# 8x8_stm32.net
KiCad netlist of a schematic drawn in EAGLE
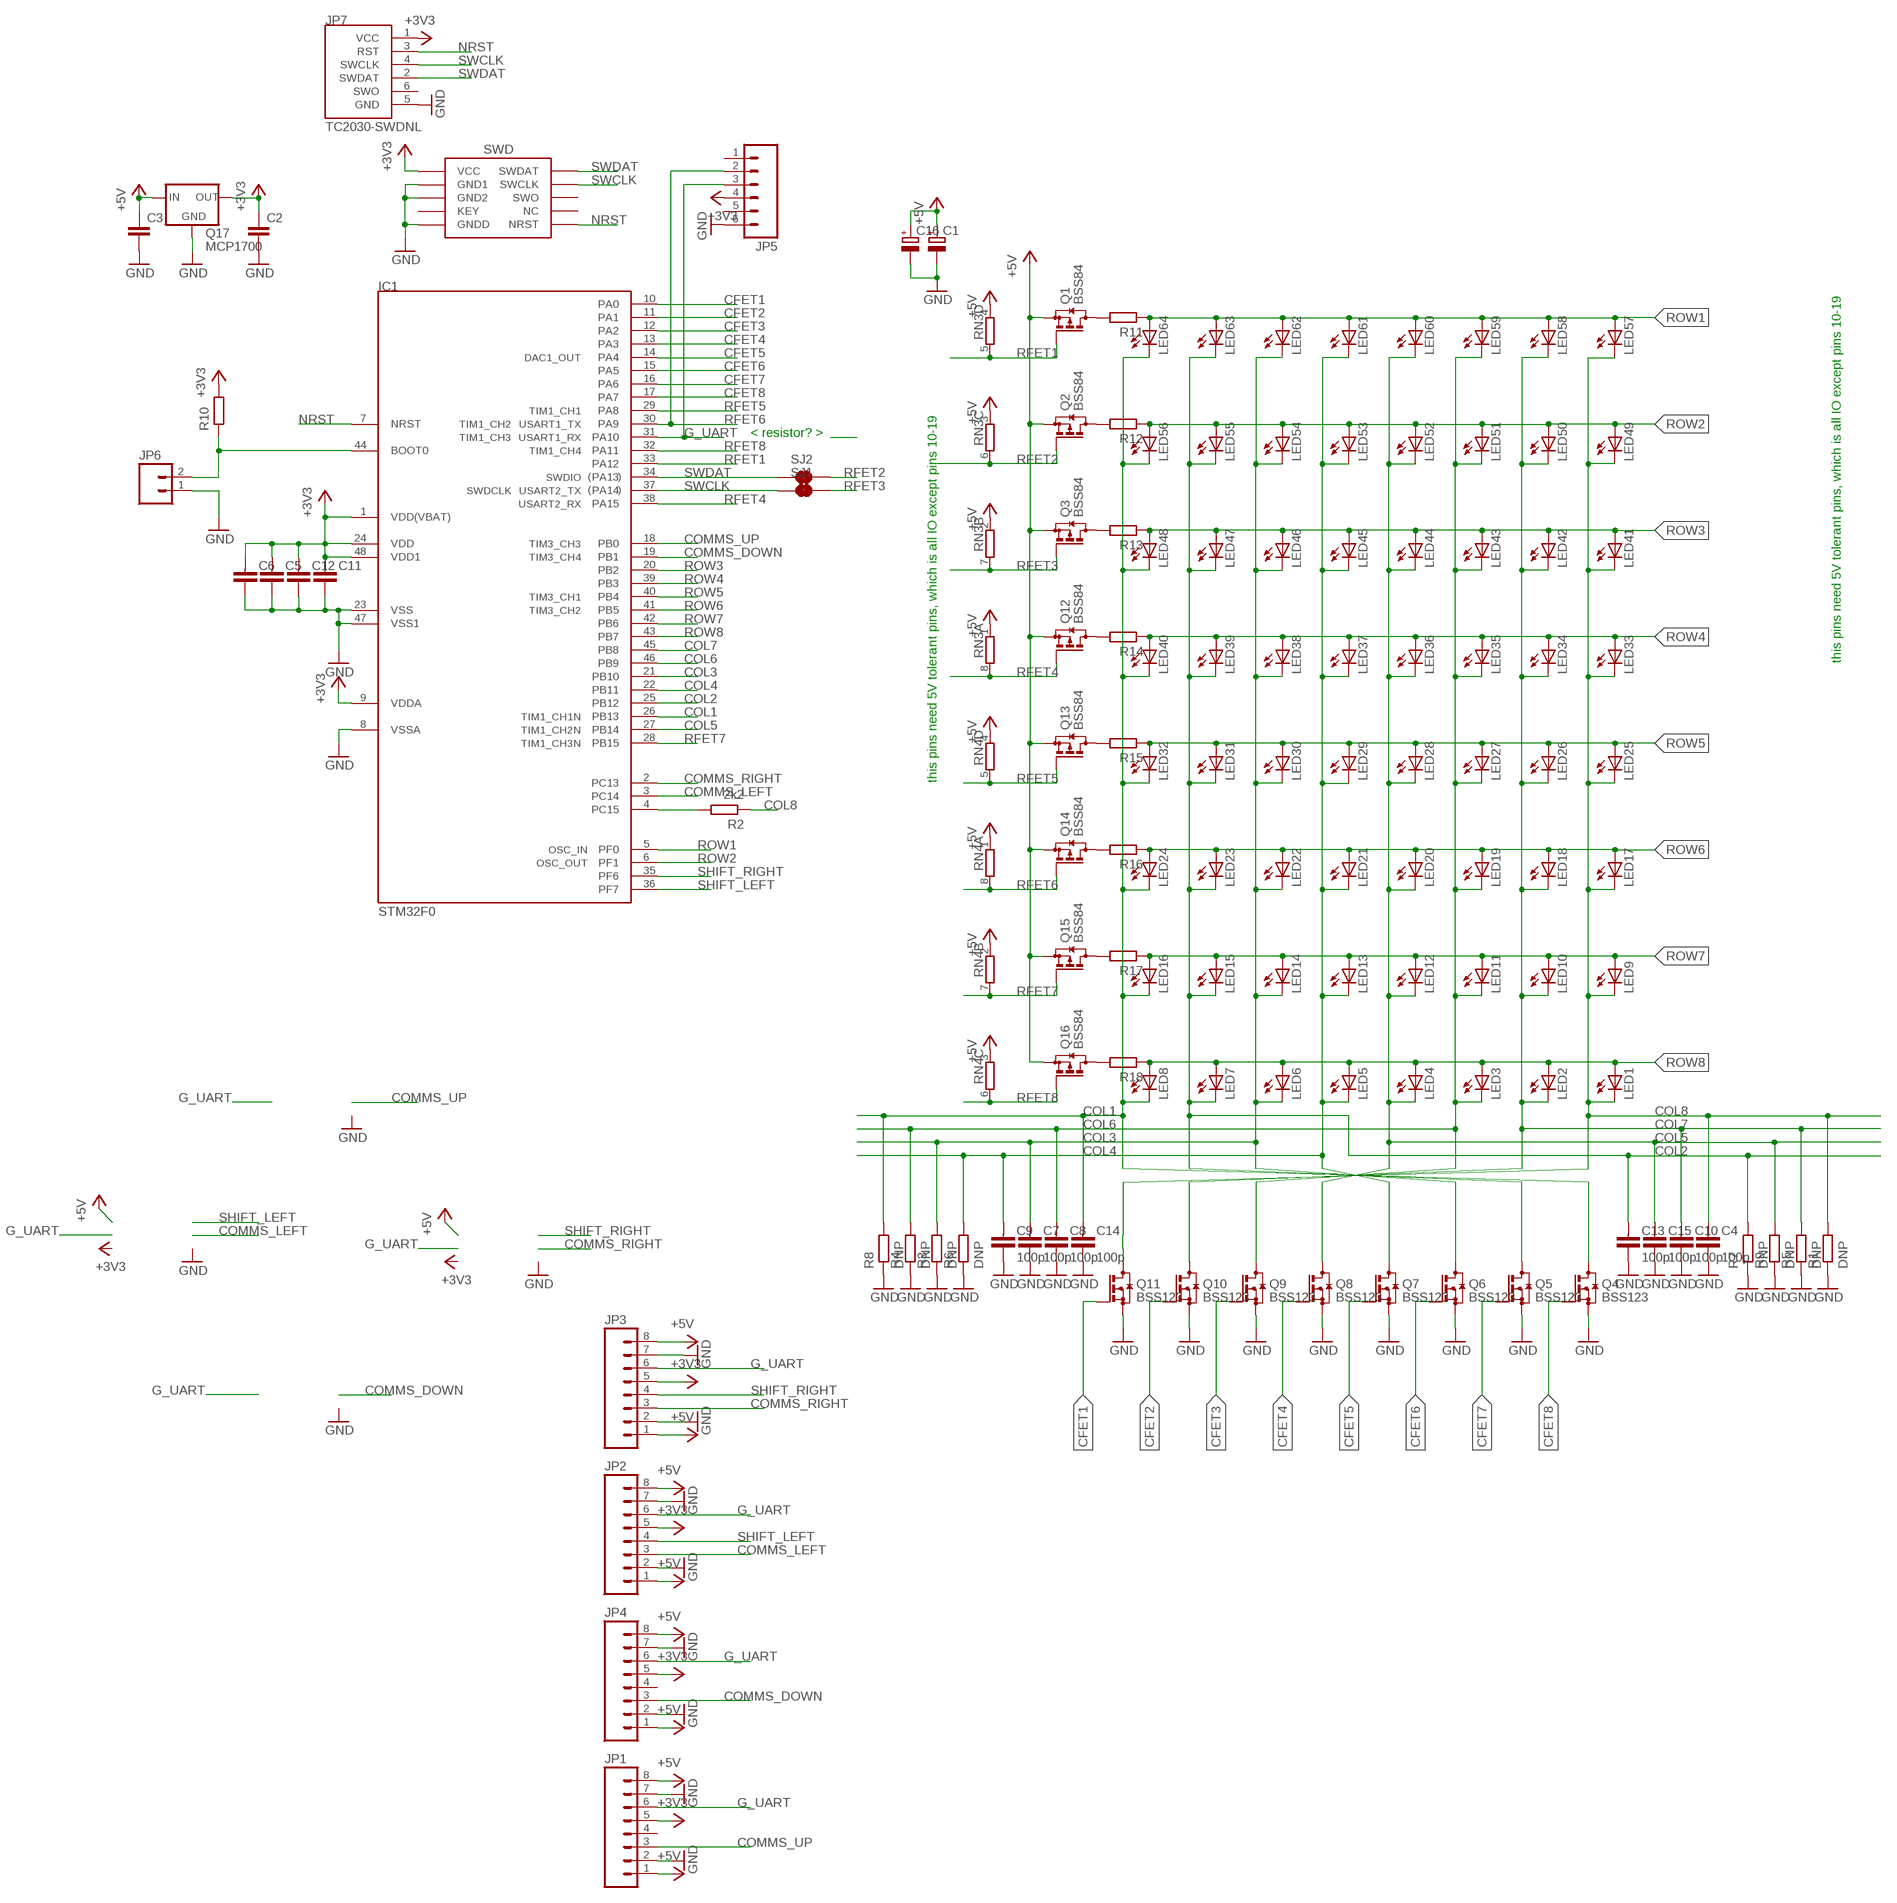
[diagram p0: schematic, sheet 1]

(export (version "E")
  (design (tool "Eeschema 10.0.6"))
  (components
    (comp (ref "C1")
      (value "CPOL-EUE2-4")
      (footprint "eagle-import:E2-4")
      (libsource (lib "eagle-import") (part "CPOL-EUE2-4"))
    )
    (comp (ref "C2")
      (value "C-EU050-025X075")
      (footprint "eagle-import:C050-025X075")
      (libsource (lib "eagle-import") (part "C-EU050-025X075"))
    )
    (comp (ref "C3")
      (value "C-EU050-025X075")
      (footprint "eagle-import:C050-025X075")
      (libsource (lib "eagle-import") (part "C-EU050-025X075"))
    )
    (comp (ref "C4")
      (value "100p")
      (footprint "eagle-import:C0603-N")
      (libsource (lib "eagle-import") (part "CAPACITOR0603-N"))
    )
    (comp (ref "C5")
      (value "CAPACITOR0603-N")
      (footprint "eagle-import:C0603-N")
      (libsource (lib "eagle-import") (part "CAPACITOR0603-N"))
    )
    (comp (ref "C6")
      (value "CAPACITOR0603-N")
      (footprint "eagle-import:C0603-N")
      (libsource (lib "eagle-import") (part "CAPACITOR0603-N"))
    )
    (comp (ref "C7")
      (value "100p")
      (footprint "eagle-import:C0603-N")
      (libsource (lib "eagle-import") (part "CAPACITOR0603-N"))
    )
    (comp (ref "C8")
      (value "100p")
      (footprint "eagle-import:C0603-N")
      (libsource (lib "eagle-import") (part "CAPACITOR0603-N"))
    )
    (comp (ref "C9")
      (value "100p")
      (footprint "eagle-import:C0603-N")
      (libsource (lib "eagle-import") (part "CAPACITOR0603-N"))
    )
    (comp (ref "C10")
      (value "100p")
      (footprint "eagle-import:C0603-N")
      (libsource (lib "eagle-import") (part "CAPACITOR0603-N"))
    )
    (comp (ref "C11")
      (value "CAPACITOR0603-N")
      (footprint "eagle-import:C0603-N")
      (libsource (lib "eagle-import") (part "CAPACITOR0603-N"))
    )
    (comp (ref "C12")
      (value "CAPACITOR0603-N")
      (footprint "eagle-import:C0603-N")
      (libsource (lib "eagle-import") (part "CAPACITOR0603-N"))
    )
    (comp (ref "C13")
      (value "100p")
      (footprint "eagle-import:C0603-N")
      (libsource (lib "eagle-import") (part "CAPACITOR0603-N"))
    )
    (comp (ref "C14")
      (value "100p")
      (footprint "eagle-import:C0603-N")
      (libsource (lib "eagle-import") (part "CAPACITOR0603-N"))
    )
    (comp (ref "C15")
      (value "100p")
      (footprint "eagle-import:C0603-N")
      (libsource (lib "eagle-import") (part "CAPACITOR0603-N"))
    )
    (comp (ref "C16")
      (value "CPOL-EUE2-4")
      (footprint "eagle-import:E2-4")
      (libsource (lib "eagle-import") (part "CPOL-EUE2-4"))
    )
    (comp (ref "IC1")
      (value "STM32F0")
      (footprint "eagle-import:TQFP48")
      (libsource (lib "eagle-import") (part "STM32F0"))
    )
    (comp (ref "J1")
      (value "SWD_SHROUD")
      (footprint "eagle-import:SWD_PTH_SHROUD")
      (libsource (lib "eagle-import") (part "SWD_SHROUD"))
    )
    (comp (ref "JP1")
      (value "M08")
      (footprint "eagle-import:1X08_ROUND")
      (libsource (lib "eagle-import") (part "M08"))
    )
    (comp (ref "JP2")
      (value "M08")
      (footprint "eagle-import:1X08_ROUND")
      (libsource (lib "eagle-import") (part "M08"))
    )
    (comp (ref "JP3")
      (value "M08")
      (footprint "eagle-import:1X08_ROUND")
      (libsource (lib "eagle-import") (part "M08"))
    )
    (comp (ref "JP4")
      (value "M08")
      (footprint "eagle-import:1X08_ROUND")
      (libsource (lib "eagle-import") (part "M08"))
    )
    (comp (ref "JP5")
      (value "M06SILK_FEMALE_PTH")
      (footprint "eagle-import:1X06")
      (libsource (lib "eagle-import") (part "M06SILK_FEMALE_PTH"))
    )
    (comp (ref "JP6")
      (value "M02PTH")
      (footprint "eagle-import:1X02")
      (libsource (lib "eagle-import") (part "M02PTH"))
    )
    (comp (ref "JP7")
      (value "TC2030-SWDNL")
      (footprint "eagle-import:TC2030-MCP-NL")
      (libsource (lib "eagle-import") (part "TC2030-SWDNL"))
    )
    (comp (ref "LED1")
      (value "LED5MM/0603")
      (footprint "eagle-import:LED5MM_SMD")
      (libsource (lib "eagle-import") (part "LED5MM/0603"))
    )
    (comp (ref "LED2")
      (value "LED5MM/0603")
      (footprint "eagle-import:LED5MM_SMD")
      (libsource (lib "eagle-import") (part "LED5MM/0603"))
    )
    (comp (ref "LED3")
      (value "LED5MM/0603")
      (footprint "eagle-import:LED5MM_SMD")
      (libsource (lib "eagle-import") (part "LED5MM/0603"))
    )
    (comp (ref "LED4")
      (value "LED5MM/0603")
      (footprint "eagle-import:LED5MM_SMD")
      (libsource (lib "eagle-import") (part "LED5MM/0603"))
    )
    (comp (ref "LED5")
      (value "LED5MM/0603")
      (footprint "eagle-import:LED5MM_SMD")
      (libsource (lib "eagle-import") (part "LED5MM/0603"))
    )
    (comp (ref "LED6")
      (value "LED5MM/0603")
      (footprint "eagle-import:LED5MM_SMD")
      (libsource (lib "eagle-import") (part "LED5MM/0603"))
    )
    (comp (ref "LED7")
      (value "LED5MM/0603")
      (footprint "eagle-import:LED5MM_SMD")
      (libsource (lib "eagle-import") (part "LED5MM/0603"))
    )
    (comp (ref "LED8")
      (value "LED5MM/0603")
      (footprint "eagle-import:LED5MM_SMD")
      (libsource (lib "eagle-import") (part "LED5MM/0603"))
    )
    (comp (ref "LED9")
      (value "LED5MM/0603")
      (footprint "eagle-import:LED5MM_SMD")
      (libsource (lib "eagle-import") (part "LED5MM/0603"))
    )
    (comp (ref "LED10")
      (value "LED5MM/0603")
      (footprint "eagle-import:LED5MM_SMD")
      (libsource (lib "eagle-import") (part "LED5MM/0603"))
    )
    (comp (ref "LED11")
      (value "LED5MM/0603")
      (footprint "eagle-import:LED5MM_SMD")
      (libsource (lib "eagle-import") (part "LED5MM/0603"))
    )
    (comp (ref "LED12")
      (value "LED5MM/0603")
      (footprint "eagle-import:LED5MM_SMD")
      (libsource (lib "eagle-import") (part "LED5MM/0603"))
    )
    (comp (ref "LED13")
      (value "LED5MM/0603")
      (footprint "eagle-import:LED5MM_SMD")
      (libsource (lib "eagle-import") (part "LED5MM/0603"))
    )
    (comp (ref "LED14")
      (value "LED5MM/0603")
      (footprint "eagle-import:LED5MM_SMD")
      (libsource (lib "eagle-import") (part "LED5MM/0603"))
    )
    (comp (ref "LED15")
      (value "LED5MM/0603")
      (footprint "eagle-import:LED5MM_SMD")
      (libsource (lib "eagle-import") (part "LED5MM/0603"))
    )
    (comp (ref "LED16")
      (value "LED5MM/0603")
      (footprint "eagle-import:LED5MM_SMD")
      (libsource (lib "eagle-import") (part "LED5MM/0603"))
    )
    (comp (ref "LED17")
      (value "LED5MM/0603")
      (footprint "eagle-import:LED5MM_SMD")
      (libsource (lib "eagle-import") (part "LED5MM/0603"))
    )
    (comp (ref "LED18")
      (value "LED5MM/0603")
      (footprint "eagle-import:LED5MM_SMD")
      (libsource (lib "eagle-import") (part "LED5MM/0603"))
    )
    (comp (ref "LED19")
      (value "LED5MM/0603")
      (footprint "eagle-import:LED5MM_SMD")
      (libsource (lib "eagle-import") (part "LED5MM/0603"))
    )
    (comp (ref "LED20")
      (value "LED5MM/0603")
      (footprint "eagle-import:LED5MM_SMD")
      (libsource (lib "eagle-import") (part "LED5MM/0603"))
    )
    (comp (ref "LED21")
      (value "LED5MM/0603")
      (footprint "eagle-import:LED5MM_SMD")
      (libsource (lib "eagle-import") (part "LED5MM/0603"))
    )
    (comp (ref "LED22")
      (value "LED5MM/0603")
      (footprint "eagle-import:LED5MM_SMD")
      (libsource (lib "eagle-import") (part "LED5MM/0603"))
    )
    (comp (ref "LED23")
      (value "LED5MM/0603")
      (footprint "eagle-import:LED5MM_SMD")
      (libsource (lib "eagle-import") (part "LED5MM/0603"))
    )
    (comp (ref "LED24")
      (value "LED5MM/0603")
      (footprint "eagle-import:LED5MM_SMD")
      (libsource (lib "eagle-import") (part "LED5MM/0603"))
    )
    (comp (ref "LED25")
      (value "LED5MM/0603")
      (footprint "eagle-import:LED5MM_SMD")
      (libsource (lib "eagle-import") (part "LED5MM/0603"))
    )
    (comp (ref "LED26")
      (value "LED5MM/0603")
      (footprint "eagle-import:LED5MM_SMD")
      (libsource (lib "eagle-import") (part "LED5MM/0603"))
    )
    (comp (ref "LED27")
      (value "LED5MM/0603")
      (footprint "eagle-import:LED5MM_SMD")
      (libsource (lib "eagle-import") (part "LED5MM/0603"))
    )
    (comp (ref "LED28")
      (value "LED5MM/0603")
      (footprint "eagle-import:LED5MM_SMD")
      (libsource (lib "eagle-import") (part "LED5MM/0603"))
    )
    (comp (ref "LED29")
      (value "LED5MM/0603")
      (footprint "eagle-import:LED5MM_SMD")
      (libsource (lib "eagle-import") (part "LED5MM/0603"))
    )
    (comp (ref "LED30")
      (value "LED5MM/0603")
      (footprint "eagle-import:LED5MM_SMD")
      (libsource (lib "eagle-import") (part "LED5MM/0603"))
    )
    (comp (ref "LED31")
      (value "LED5MM/0603")
      (footprint "eagle-import:LED5MM_SMD")
      (libsource (lib "eagle-import") (part "LED5MM/0603"))
    )
    (comp (ref "LED32")
      (value "LED5MM/0603")
      (footprint "eagle-import:LED5MM_SMD")
      (libsource (lib "eagle-import") (part "LED5MM/0603"))
    )
    (comp (ref "LED33")
      (value "LED5MM/0603")
      (footprint "eagle-import:LED5MM_SMD")
      (libsource (lib "eagle-import") (part "LED5MM/0603"))
    )
    (comp (ref "LED34")
      (value "LED5MM/0603")
      (footprint "eagle-import:LED5MM_SMD")
      (libsource (lib "eagle-import") (part "LED5MM/0603"))
    )
    (comp (ref "LED35")
      (value "LED5MM/0603")
      (footprint "eagle-import:LED5MM_SMD")
      (libsource (lib "eagle-import") (part "LED5MM/0603"))
    )
    (comp (ref "LED36")
      (value "LED5MM/0603")
      (footprint "eagle-import:LED5MM_SMD")
      (libsource (lib "eagle-import") (part "LED5MM/0603"))
    )
    (comp (ref "LED37")
      (value "LED5MM/0603")
      (footprint "eagle-import:LED5MM_SMD")
      (libsource (lib "eagle-import") (part "LED5MM/0603"))
    )
    (comp (ref "LED38")
      (value "LED5MM/0603")
      (footprint "eagle-import:LED5MM_SMD")
      (libsource (lib "eagle-import") (part "LED5MM/0603"))
    )
    (comp (ref "LED39")
      (value "LED5MM/0603")
      (footprint "eagle-import:LED5MM_SMD")
      (libsource (lib "eagle-import") (part "LED5MM/0603"))
    )
    (comp (ref "LED40")
      (value "LED5MM/0603")
      (footprint "eagle-import:LED5MM_SMD")
      (libsource (lib "eagle-import") (part "LED5MM/0603"))
    )
    (comp (ref "LED41")
      (value "LED5MM/0603")
      (footprint "eagle-import:LED5MM_SMD")
      (libsource (lib "eagle-import") (part "LED5MM/0603"))
    )
    (comp (ref "LED42")
      (value "LED5MM/0603")
      (footprint "eagle-import:LED5MM_SMD")
      (libsource (lib "eagle-import") (part "LED5MM/0603"))
    )
    (comp (ref "LED43")
      (value "LED5MM/0603")
      (footprint "eagle-import:LED5MM_SMD")
      (libsource (lib "eagle-import") (part "LED5MM/0603"))
    )
    (comp (ref "LED44")
      (value "LED5MM/0603")
      (footprint "eagle-import:LED5MM_SMD")
      (libsource (lib "eagle-import") (part "LED5MM/0603"))
    )
    (comp (ref "LED45")
      (value "LED5MM/0603")
      (footprint "eagle-import:LED5MM_SMD")
      (libsource (lib "eagle-import") (part "LED5MM/0603"))
    )
    (comp (ref "LED46")
      (value "LED5MM/0603")
      (footprint "eagle-import:LED5MM_SMD")
      (libsource (lib "eagle-import") (part "LED5MM/0603"))
    )
    (comp (ref "LED47")
      (value "LED5MM/0603")
      (footprint "eagle-import:LED5MM_SMD")
      (libsource (lib "eagle-import") (part "LED5MM/0603"))
    )
    (comp (ref "LED48")
      (value "LED5MM/0603")
      (footprint "eagle-import:LED5MM_SMD")
      (libsource (lib "eagle-import") (part "LED5MM/0603"))
    )
    (comp (ref "LED49")
      (value "LED5MM/0603")
      (footprint "eagle-import:LED5MM_SMD")
      (libsource (lib "eagle-import") (part "LED5MM/0603"))
    )
    (comp (ref "LED50")
      (value "LED5MM/0603")
      (footprint "eagle-import:LED5MM_SMD")
      (libsource (lib "eagle-import") (part "LED5MM/0603"))
    )
    (comp (ref "LED51")
      (value "LED5MM/0603")
      (footprint "eagle-import:LED5MM_SMD")
      (libsource (lib "eagle-import") (part "LED5MM/0603"))
    )
    (comp (ref "LED52")
      (value "LED5MM/0603")
      (footprint "eagle-import:LED5MM_SMD")
      (libsource (lib "eagle-import") (part "LED5MM/0603"))
    )
    (comp (ref "LED53")
      (value "LED5MM/0603")
      (footprint "eagle-import:LED5MM_SMD")
      (libsource (lib "eagle-import") (part "LED5MM/0603"))
    )
    (comp (ref "LED54")
      (value "LED5MM/0603")
      (footprint "eagle-import:LED5MM_SMD")
      (libsource (lib "eagle-import") (part "LED5MM/0603"))
    )
    (comp (ref "LED55")
      (value "LED5MM/0603")
      (footprint "eagle-import:LED5MM_SMD")
      (libsource (lib "eagle-import") (part "LED5MM/0603"))
    )
    (comp (ref "LED56")
      (value "LED5MM/0603")
      (footprint "eagle-import:LED5MM_SMD")
      (libsource (lib "eagle-import") (part "LED5MM/0603"))
    )
    (comp (ref "LED57")
      (value "LED5MM/0603")
      (footprint "eagle-import:LED5MM_SMD")
      (libsource (lib "eagle-import") (part "LED5MM/0603"))
    )
    (comp (ref "LED58")
      (value "LED5MM/0603")
      (footprint "eagle-import:LED5MM_SMD")
      (libsource (lib "eagle-import") (part "LED5MM/0603"))
    )
    (comp (ref "LED59")
      (value "LED5MM/0603")
      (footprint "eagle-import:LED5MM_SMD")
      (libsource (lib "eagle-import") (part "LED5MM/0603"))
    )
    (comp (ref "LED60")
      (value "LED5MM/0603")
      (footprint "eagle-import:LED5MM_SMD")
      (libsource (lib "eagle-import") (part "LED5MM/0603"))
    )
    (comp (ref "LED61")
      (value "LED5MM/0603")
      (footprint "eagle-import:LED5MM_SMD")
      (libsource (lib "eagle-import") (part "LED5MM/0603"))
    )
    (comp (ref "LED62")
      (value "LED5MM/0603")
      (footprint "eagle-import:LED5MM_SMD")
      (libsource (lib "eagle-import") (part "LED5MM/0603"))
    )
    (comp (ref "LED63")
      (value "LED5MM/0603")
      (footprint "eagle-import:LED5MM_SMD")
      (libsource (lib "eagle-import") (part "LED5MM/0603"))
    )
    (comp (ref "LED64")
      (value "LED5MM/0603")
      (footprint "eagle-import:LED5MM_SMD")
      (libsource (lib "eagle-import") (part "LED5MM/0603"))
    )
    (comp (ref "Q1")
      (value "BSS84")
      (footprint "eagle-import:SOT23")
      (libsource (lib "eagle-import") (part "BSS84"))
    )
    (comp (ref "Q2")
      (value "BSS84")
      (footprint "eagle-import:SOT23")
      (libsource (lib "eagle-import") (part "BSS84"))
    )
    (comp (ref "Q3")
      (value "BSS84")
      (footprint "eagle-import:SOT23")
      (libsource (lib "eagle-import") (part "BSS84"))
    )
    (comp (ref "Q4")
      (value "BSS123")
      (footprint "eagle-import:SOT23")
      (libsource (lib "eagle-import") (part "BSS123"))
    )
    (comp (ref "Q5")
      (value "BSS123")
      (footprint "eagle-import:SOT23")
      (libsource (lib "eagle-import") (part "BSS123"))
    )
    (comp (ref "Q6")
      (value "BSS123")
      (footprint "eagle-import:SOT23")
      (libsource (lib "eagle-import") (part "BSS123"))
    )
    (comp (ref "Q7")
      (value "BSS123")
      (footprint "eagle-import:SOT23")
      (libsource (lib "eagle-import") (part "BSS123"))
    )
    (comp (ref "Q8")
      (value "BSS123")
      (footprint "eagle-import:SOT23")
      (libsource (lib "eagle-import") (part "BSS123"))
    )
    (comp (ref "Q9")
      (value "BSS123")
      (footprint "eagle-import:SOT23")
      (libsource (lib "eagle-import") (part "BSS123"))
    )
    (comp (ref "Q10")
      (value "BSS123")
      (footprint "eagle-import:SOT23")
      (libsource (lib "eagle-import") (part "BSS123"))
    )
    (comp (ref "Q11")
      (value "BSS123")
      (footprint "eagle-import:SOT23")
      (libsource (lib "eagle-import") (part "BSS123"))
    )
    (comp (ref "Q12")
      (value "BSS84")
      (footprint "eagle-import:SOT23")
      (libsource (lib "eagle-import") (part "BSS84"))
    )
    (comp (ref "Q13")
      (value "BSS84")
      (footprint "eagle-import:SOT23")
      (libsource (lib "eagle-import") (part "BSS84"))
    )
    (comp (ref "Q14")
      (value "BSS84")
      (footprint "eagle-import:SOT23")
      (libsource (lib "eagle-import") (part "BSS84"))
    )
    (comp (ref "Q15")
      (value "BSS84")
      (footprint "eagle-import:SOT23")
      (libsource (lib "eagle-import") (part "BSS84"))
    )
    (comp (ref "Q16")
      (value "BSS84")
      (footprint "eagle-import:SOT23")
      (libsource (lib "eagle-import") (part "BSS84"))
    )
    (comp (ref "Q17")
      (value "MCP1700")
      (footprint "eagle-import:TO92-INLINE")
      (libsource (lib "eagle-import") (part "MCP1700"))
    )
    (comp (ref "R1")
      (value "DNP")
      (footprint "eagle-import:R0603-N")
      (libsource (lib "eagle-import") (part "RESISTOR0603-N"))
    )
    (comp (ref "R2")
      (value "2k2")
      (footprint "eagle-import:R0603-N")
      (libsource (lib "eagle-import") (part "RESISTOR0603-N"))
    )
    (comp (ref "R3")
      (value "DNP")
      (footprint "eagle-import:R0603-N")
      (libsource (lib "eagle-import") (part "RESISTOR0603-N"))
    )
    (comp (ref "R4")
      (value "DNP")
      (footprint "eagle-import:R0603-N")
      (libsource (lib "eagle-import") (part "RESISTOR0603-N"))
    )
    (comp (ref "R5")
      (value "DNP")
      (footprint "eagle-import:R0603-N")
      (libsource (lib "eagle-import") (part "RESISTOR0603-N"))
    )
    (comp (ref "R6")
      (value "DNP")
      (footprint "eagle-import:R0603-N")
      (libsource (lib "eagle-import") (part "RESISTOR0603-N"))
    )
    (comp (ref "R7")
      (value "DNP")
      (footprint "eagle-import:R0603-N")
      (libsource (lib "eagle-import") (part "RESISTOR0603-N"))
    )
    (comp (ref "R8")
      (value "DNP")
      (footprint "eagle-import:R0603-N")
      (libsource (lib "eagle-import") (part "RESISTOR0603-N"))
    )
    (comp (ref "R9")
      (value "DNP")
      (footprint "eagle-import:R0603-N")
      (libsource (lib "eagle-import") (part "RESISTOR0603-N"))
    )
    (comp (ref "R10")
      (value "RESISTOR0603-N")
      (footprint "eagle-import:R0603-N")
      (libsource (lib "eagle-import") (part "RESISTOR0603-N"))
    )
    (comp (ref "R11")
      (value "RESISTOR0603-N")
      (footprint "eagle-import:R0603-N")
      (libsource (lib "eagle-import") (part "RESISTOR0603-N"))
    )
    (comp (ref "R12")
      (value "RESISTOR0603-N")
      (footprint "eagle-import:R0603-N")
      (libsource (lib "eagle-import") (part "RESISTOR0603-N"))
    )
    (comp (ref "R13")
      (value "RESISTOR0603-N")
      (footprint "eagle-import:R0603-N")
      (libsource (lib "eagle-import") (part "RESISTOR0603-N"))
    )
    (comp (ref "R14")
      (value "RESISTOR0603-N")
      (footprint "eagle-import:R0603-N")
      (libsource (lib "eagle-import") (part "RESISTOR0603-N"))
    )
    (comp (ref "R15")
      (value "RESISTOR0603-N")
      (footprint "eagle-import:R0603-N")
      (libsource (lib "eagle-import") (part "RESISTOR0603-N"))
    )
    (comp (ref "R16")
      (value "RESISTOR0603-N")
      (footprint "eagle-import:R0603-N")
      (libsource (lib "eagle-import") (part "RESISTOR0603-N"))
    )
    (comp (ref "R17")
      (value "RESISTOR0603-N")
      (footprint "eagle-import:R0603-N")
      (libsource (lib "eagle-import") (part "RESISTOR0603-N"))
    )
    (comp (ref "R18")
      (value "RESISTOR0603-N")
      (footprint "eagle-import:R0603-N")
      (libsource (lib "eagle-import") (part "RESISTOR0603-N"))
    )
    (comp (ref "RN3")
      (value "4R-NEXB38V")
      (footprint "eagle-import:EXB38V")
      (libsource (lib "eagle-import") (part "4R-NEXB38V"))
    )
    (comp (ref "RN4")
      (value "4R-NEXB38V")
      (footprint "eagle-import:EXB38V")
      (libsource (lib "eagle-import") (part "4R-NEXB38V"))
    )
    (comp (ref "SJ1")
      (value "JUMPER-PAD-2-NC_BY_TRACE")
      (footprint "eagle-import:PAD-JUMPER-2-NC_BY_TRACE_YES_SILK")
      (libsource (lib "eagle-import") (part "JUMPER-PAD-2-NC_BY_TRACE"))
    )
    (comp (ref "SJ2")
      (value "JUMPER-PAD-2-NC_BY_TRACE")
      (footprint "eagle-import:PAD-JUMPER-2-NC_BY_TRACE_YES_SILK")
      (libsource (lib "eagle-import") (part "JUMPER-PAD-2-NC_BY_TRACE"))
    )
  )
  (nets
    (net (code "1") (name "+3V3") (class "Default")
      (node (ref "C11") (pin "1") (pinfunction "1_1") (pintype "passive"))
      (node (ref "C12") (pin "1") (pinfunction "1_1") (pintype "passive"))
      (node (ref "C2") (pin "1") (pinfunction "1_1") (pintype "passive"))
      (node (ref "C5") (pin "1") (pinfunction "1_1") (pintype "passive"))
      (node (ref "C6") (pin "1") (pinfunction "1_1") (pintype "passive"))
      (node (ref "IC1") (pin "1") (pinfunction "VDD(VBAT)_1") (pintype "power_in"))
      (node (ref "IC1") (pin "24") (pinfunction "VDD_24") (pintype "power_in"))
      (node (ref "IC1") (pin "48") (pinfunction "VDD1_48") (pintype "power_in"))
      (node (ref "IC1") (pin "9") (pinfunction "VDDA_9") (pintype "power_in"))
      (node (ref "J1") (pin "1") (pinfunction "VCC_1") (pintype "power_in"))
      (node (ref "JP1") (pin "5") (pinfunction "5_5") (pintype "passive"))
      (node (ref "JP2") (pin "5") (pinfunction "5_5") (pintype "passive"))
      (node (ref "JP3") (pin "5") (pinfunction "5_5") (pintype "passive"))
      (node (ref "JP4") (pin "5") (pinfunction "5_5") (pintype "passive"))
      (node (ref "JP5") (pin "4") (pinfunction "4_4") (pintype "passive"))
      (node (ref "JP7") (pin "1") (pinfunction "VCC_1") (pintype "power_in"))
      (node (ref "Q17") (pin "VOUT") (pinfunction "OUT_VOUT") (pintype "passive"))
      (node (ref "R10") (pin "2") (pinfunction "P$2_2") (pintype "passive"))
    )
    (net (code "2") (name "+5V") (class "Default")
      (node (ref "C1") (pin "+") (pinfunction "+_+") (pintype "passive"))
      (node (ref "C16") (pin "+") (pinfunction "+_+") (pintype "passive"))
      (node (ref "C3") (pin "1") (pinfunction "1_1") (pintype "passive"))
      (node (ref "JP1") (pin "1") (pinfunction "1_1") (pintype "passive"))
      (node (ref "JP1") (pin "8") (pinfunction "8_8") (pintype "passive"))
      (node (ref "JP2") (pin "1") (pinfunction "1_1") (pintype "passive"))
      (node (ref "JP2") (pin "8") (pinfunction "8_8") (pintype "passive"))
      (node (ref "JP3") (pin "1") (pinfunction "1_1") (pintype "passive"))
      (node (ref "JP3") (pin "8") (pinfunction "8_8") (pintype "passive"))
      (node (ref "JP4") (pin "1") (pinfunction "1_1") (pintype "passive"))
      (node (ref "JP4") (pin "8") (pinfunction "8_8") (pintype "passive"))
      (node (ref "Q1") (pin "2") (pinfunction "S_2") (pintype "passive"))
      (node (ref "Q12") (pin "2") (pinfunction "S_2") (pintype "passive"))
      (node (ref "Q13") (pin "2") (pinfunction "S_2") (pintype "passive"))
      (node (ref "Q14") (pin "2") (pinfunction "S_2") (pintype "passive"))
      (node (ref "Q15") (pin "2") (pinfunction "S_2") (pintype "passive"))
      (node (ref "Q16") (pin "2") (pinfunction "S_2") (pintype "passive"))
      (node (ref "Q17") (pin "VIN") (pinfunction "IN_VIN") (pintype "input"))
      (node (ref "Q2") (pin "2") (pinfunction "S_2") (pintype "passive"))
      (node (ref "Q3") (pin "2") (pinfunction "S_2") (pintype "passive"))
      (node (ref "RN3") (pin "1") (pinfunction "1_1") (pintype "passive"))
      (node (ref "RN3") (pin "2") (pinfunction "1_2") (pintype "passive"))
      (node (ref "RN3") (pin "3") (pinfunction "1_3") (pintype "passive"))
      (node (ref "RN3") (pin "4") (pinfunction "1_4") (pintype "passive"))
      (node (ref "RN4") (pin "1") (pinfunction "1_1") (pintype "passive"))
      (node (ref "RN4") (pin "2") (pinfunction "1_2") (pintype "passive"))
      (node (ref "RN4") (pin "3") (pinfunction "1_3") (pintype "passive"))
      (node (ref "RN4") (pin "4") (pinfunction "1_4") (pintype "passive"))
    )
    (net (code "3") (name "/COL1") (class "Default")
      (node (ref "C14") (pin "1") (pinfunction "1_1") (pintype "passive"))
      (node (ref "IC1") (pin "26") (pinfunction "PB13_26") (pintype "bidirectional"))
      (node (ref "LED16") (pin "K") (pinfunction "C_K") (pintype "passive"))
      (node (ref "LED16") (pin "K1") (pinfunction "C_K1") (pintype "passive"))
      (node (ref "LED24") (pin "K") (pinfunction "C_K") (pintype "passive"))
      (node (ref "LED24") (pin "K1") (pinfunction "C_K1") (pintype "passive"))
      (node (ref "LED32") (pin "K") (pinfunction "C_K") (pintype "passive"))
      (node (ref "LED32") (pin "K1") (pinfunction "C_K1") (pintype "passive"))
      (node (ref "LED40") (pin "K") (pinfunction "C_K") (pintype "passive"))
      (node (ref "LED40") (pin "K1") (pinfunction "C_K1") (pintype "passive"))
      (node (ref "LED48") (pin "K") (pinfunction "C_K") (pintype "passive"))
      (node (ref "LED48") (pin "K1") (pinfunction "C_K1") (pintype "passive"))
      (node (ref "LED56") (pin "K") (pinfunction "C_K") (pintype "passive"))
      (node (ref "LED56") (pin "K1") (pinfunction "C_K1") (pintype "passive"))
      (node (ref "LED64") (pin "K") (pinfunction "C_K") (pintype "passive"))
      (node (ref "LED64") (pin "K1") (pinfunction "C_K1") (pintype "passive"))
      (node (ref "LED8") (pin "K") (pinfunction "C_K") (pintype "passive"))
      (node (ref "LED8") (pin "K1") (pinfunction "C_K1") (pintype "passive"))
      (node (ref "Q4") (pin "3") (pinfunction "D_3") (pintype "passive"))
      (node (ref "R8") (pin "2") (pinfunction "P$2_2") (pintype "passive"))
    )
    (net (code "4") (name "/COL2") (class "Default")
      (node (ref "C13") (pin "1") (pinfunction "1_1") (pintype "passive"))
      (node (ref "IC1") (pin "25") (pinfunction "PB12_25") (pintype "bidirectional"))
      (node (ref "LED15") (pin "K") (pinfunction "C_K") (pintype "passive"))
      (node (ref "LED15") (pin "K1") (pinfunction "C_K1") (pintype "passive"))
      (node (ref "LED23") (pin "K") (pinfunction "C_K") (pintype "passive"))
      (node (ref "LED23") (pin "K1") (pinfunction "C_K1") (pintype "passive"))
      (node (ref "LED31") (pin "K") (pinfunction "C_K") (pintype "passive"))
      (node (ref "LED31") (pin "K1") (pinfunction "C_K1") (pintype "passive"))
      (node (ref "LED39") (pin "K") (pinfunction "C_K") (pintype "passive"))
      (node (ref "LED39") (pin "K1") (pinfunction "C_K1") (pintype "passive"))
      (node (ref "LED47") (pin "K") (pinfunction "C_K") (pintype "passive"))
      (node (ref "LED47") (pin "K1") (pinfunction "C_K1") (pintype "passive"))
      (node (ref "LED55") (pin "K") (pinfunction "C_K") (pintype "passive"))
      (node (ref "LED55") (pin "K1") (pinfunction "C_K1") (pintype "passive"))
      (node (ref "LED63") (pin "K") (pinfunction "C_K") (pintype "passive"))
      (node (ref "LED63") (pin "K1") (pinfunction "C_K1") (pintype "passive"))
      (node (ref "LED7") (pin "K") (pinfunction "C_K") (pintype "passive"))
      (node (ref "LED7") (pin "K1") (pinfunction "C_K1") (pintype "passive"))
      (node (ref "Q5") (pin "3") (pinfunction "D_3") (pintype "passive"))
      (node (ref "R7") (pin "2") (pinfunction "P$2_2") (pintype "passive"))
    )
    (net (code "5") (name "/COL3") (class "Default")
      (node (ref "C7") (pin "1") (pinfunction "1_1") (pintype "passive"))
      (node (ref "IC1") (pin "21") (pinfunction "PB10_21") (pintype "bidirectional"))
      (node (ref "LED14") (pin "K") (pinfunction "C_K") (pintype "passive"))
      (node (ref "LED14") (pin "K1") (pinfunction "C_K1") (pintype "passive"))
      (node (ref "LED22") (pin "K") (pinfunction "C_K") (pintype "passive"))
      (node (ref "LED22") (pin "K1") (pinfunction "C_K1") (pintype "passive"))
      (node (ref "LED30") (pin "K") (pinfunction "C_K") (pintype "passive"))
      (node (ref "LED30") (pin "K1") (pinfunction "C_K1") (pintype "passive"))
      (node (ref "LED38") (pin "K") (pinfunction "C_K") (pintype "passive"))
      (node (ref "LED38") (pin "K1") (pinfunction "C_K1") (pintype "passive"))
      (node (ref "LED46") (pin "K") (pinfunction "C_K") (pintype "passive"))
      (node (ref "LED46") (pin "K1") (pinfunction "C_K1") (pintype "passive"))
      (node (ref "LED54") (pin "K") (pinfunction "C_K") (pintype "passive"))
      (node (ref "LED54") (pin "K1") (pinfunction "C_K1") (pintype "passive"))
      (node (ref "LED6") (pin "K") (pinfunction "C_K") (pintype "passive"))
      (node (ref "LED6") (pin "K1") (pinfunction "C_K1") (pintype "passive"))
      (node (ref "LED62") (pin "K") (pinfunction "C_K") (pintype "passive"))
      (node (ref "LED62") (pin "K1") (pinfunction "C_K1") (pintype "passive"))
      (node (ref "Q6") (pin "3") (pinfunction "D_3") (pintype "passive"))
      (node (ref "R3") (pin "2") (pinfunction "P$2_2") (pintype "passive"))
    )
    (net (code "6") (name "/COL4") (class "Default")
      (node (ref "C9") (pin "1") (pinfunction "1_1") (pintype "passive"))
      (node (ref "IC1") (pin "22") (pinfunction "PB11_22") (pintype "bidirectional"))
      (node (ref "LED13") (pin "K") (pinfunction "C_K") (pintype "passive"))
      (node (ref "LED13") (pin "K1") (pinfunction "C_K1") (pintype "passive"))
      (node (ref "LED21") (pin "K") (pinfunction "C_K") (pintype "passive"))
      (node (ref "LED21") (pin "K1") (pinfunction "C_K1") (pintype "passive"))
      (node (ref "LED29") (pin "K") (pinfunction "C_K") (pintype "passive"))
      (node (ref "LED29") (pin "K1") (pinfunction "C_K1") (pintype "passive"))
      (node (ref "LED37") (pin "K") (pinfunction "C_K") (pintype "passive"))
      (node (ref "LED37") (pin "K1") (pinfunction "C_K1") (pintype "passive"))
      (node (ref "LED45") (pin "K") (pinfunction "C_K") (pintype "passive"))
      (node (ref "LED45") (pin "K1") (pinfunction "C_K1") (pintype "passive"))
      (node (ref "LED5") (pin "K") (pinfunction "C_K") (pintype "passive"))
      (node (ref "LED5") (pin "K1") (pinfunction "C_K1") (pintype "passive"))
      (node (ref "LED53") (pin "K") (pinfunction "C_K") (pintype "passive"))
      (node (ref "LED53") (pin "K1") (pinfunction "C_K1") (pintype "passive"))
      (node (ref "LED61") (pin "K") (pinfunction "C_K") (pintype "passive"))
      (node (ref "LED61") (pin "K1") (pinfunction "C_K1") (pintype "passive"))
      (node (ref "Q7") (pin "3") (pinfunction "D_3") (pintype "passive"))
      (node (ref "R6") (pin "2") (pinfunction "P$2_2") (pintype "passive"))
    )
    (net (code "7") (name "/COL5") (class "Default")
      (node (ref "C15") (pin "1") (pinfunction "1_1") (pintype "passive"))
      (node (ref "IC1") (pin "27") (pinfunction "PB14_27") (pintype "bidirectional"))
      (node (ref "LED12") (pin "K") (pinfunction "C_K") (pintype "passive"))
      (node (ref "LED12") (pin "K1") (pinfunction "C_K1") (pintype "passive"))
      (node (ref "LED20") (pin "K") (pinfunction "C_K") (pintype "passive"))
      (node (ref "LED20") (pin "K1") (pinfunction "C_K1") (pintype "passive"))
      (node (ref "LED28") (pin "K") (pinfunction "C_K") (pintype "passive"))
      (node (ref "LED28") (pin "K1") (pinfunction "C_K1") (pintype "passive"))
      (node (ref "LED36") (pin "K") (pinfunction "C_K") (pintype "passive"))
      (node (ref "LED36") (pin "K1") (pinfunction "C_K1") (pintype "passive"))
      (node (ref "LED4") (pin "K") (pinfunction "C_K") (pintype "passive"))
      (node (ref "LED4") (pin "K1") (pinfunction "C_K1") (pintype "passive"))
      (node (ref "LED44") (pin "K") (pinfunction "C_K") (pintype "passive"))
      (node (ref "LED44") (pin "K1") (pinfunction "C_K1") (pintype "passive"))
      (node (ref "LED52") (pin "K") (pinfunction "C_K") (pintype "passive"))
      (node (ref "LED52") (pin "K1") (pinfunction "C_K1") (pintype "passive"))
      (node (ref "LED60") (pin "K") (pinfunction "C_K") (pintype "passive"))
      (node (ref "LED60") (pin "K1") (pinfunction "C_K1") (pintype "passive"))
      (node (ref "Q8") (pin "3") (pinfunction "D_3") (pintype "passive"))
      (node (ref "R9") (pin "2") (pinfunction "P$2_2") (pintype "passive"))
    )
    (net (code "8") (name "/COL6") (class "Default")
      (node (ref "C8") (pin "1") (pinfunction "1_1") (pintype "passive"))
      (node (ref "IC1") (pin "46") (pinfunction "PB9_46") (pintype "bidirectional"))
      (node (ref "LED11") (pin "K") (pinfunction "C_K") (pintype "passive"))
      (node (ref "LED11") (pin "K1") (pinfunction "C_K1") (pintype "passive"))
      (node (ref "LED19") (pin "K") (pinfunction "C_K") (pintype "passive"))
      (node (ref "LED19") (pin "K1") (pinfunction "C_K1") (pintype "passive"))
      (node (ref "LED27") (pin "K") (pinfunction "C_K") (pintype "passive"))
      (node (ref "LED27") (pin "K1") (pinfunction "C_K1") (pintype "passive"))
      (node (ref "LED3") (pin "K") (pinfunction "C_K") (pintype "passive"))
      (node (ref "LED3") (pin "K1") (pinfunction "C_K1") (pintype "passive"))
      (node (ref "LED35") (pin "K") (pinfunction "C_K") (pintype "passive"))
      (node (ref "LED35") (pin "K1") (pinfunction "C_K1") (pintype "passive"))
      (node (ref "LED43") (pin "K") (pinfunction "C_K") (pintype "passive"))
      (node (ref "LED43") (pin "K1") (pinfunction "C_K1") (pintype "passive"))
      (node (ref "LED51") (pin "K") (pinfunction "C_K") (pintype "passive"))
      (node (ref "LED51") (pin "K1") (pinfunction "C_K1") (pintype "passive"))
      (node (ref "LED59") (pin "K") (pinfunction "C_K") (pintype "passive"))
      (node (ref "LED59") (pin "K1") (pinfunction "C_K1") (pintype "passive"))
      (node (ref "Q9") (pin "3") (pinfunction "D_3") (pintype "passive"))
      (node (ref "R4") (pin "2") (pinfunction "P$2_2") (pintype "passive"))
    )
    (net (code "9") (name "/COL7") (class "Default")
      (node (ref "C10") (pin "1") (pinfunction "1_1") (pintype "passive"))
      (node (ref "IC1") (pin "45") (pinfunction "PB8_45") (pintype "bidirectional"))
      (node (ref "LED10") (pin "K") (pinfunction "C_K") (pintype "passive"))
      (node (ref "LED10") (pin "K1") (pinfunction "C_K1") (pintype "passive"))
      (node (ref "LED18") (pin "K") (pinfunction "C_K") (pintype "passive"))
      (node (ref "LED18") (pin "K1") (pinfunction "C_K1") (pintype "passive"))
      (node (ref "LED2") (pin "K") (pinfunction "C_K") (pintype "passive"))
      (node (ref "LED2") (pin "K1") (pinfunction "C_K1") (pintype "passive"))
      (node (ref "LED26") (pin "K") (pinfunction "C_K") (pintype "passive"))
      (node (ref "LED26") (pin "K1") (pinfunction "C_K1") (pintype "passive"))
      (node (ref "LED34") (pin "K") (pinfunction "C_K") (pintype "passive"))
      (node (ref "LED34") (pin "K1") (pinfunction "C_K1") (pintype "passive"))
      (node (ref "LED42") (pin "K") (pinfunction "C_K") (pintype "passive"))
      (node (ref "LED42") (pin "K1") (pinfunction "C_K1") (pintype "passive"))
      (node (ref "LED50") (pin "K") (pinfunction "C_K") (pintype "passive"))
      (node (ref "LED50") (pin "K1") (pinfunction "C_K1") (pintype "passive"))
      (node (ref "LED58") (pin "K") (pinfunction "C_K") (pintype "passive"))
      (node (ref "LED58") (pin "K1") (pinfunction "C_K1") (pintype "passive"))
      (node (ref "Q10") (pin "3") (pinfunction "D_3") (pintype "passive"))
      (node (ref "R5") (pin "2") (pinfunction "P$2_2") (pintype "passive"))
    )
    (net (code "10") (name "/COL8") (class "Default")
      (node (ref "C4") (pin "1") (pinfunction "1_1") (pintype "passive"))
      (node (ref "LED1") (pin "K") (pinfunction "C_K") (pintype "passive"))
      (node (ref "LED1") (pin "K1") (pinfunction "C_K1") (pintype "passive"))
      (node (ref "LED17") (pin "K") (pinfunction "C_K") (pintype "passive"))
      (node (ref "LED17") (pin "K1") (pinfunction "C_K1") (pintype "passive"))
      (node (ref "LED25") (pin "K") (pinfunction "C_K") (pintype "passive"))
      (node (ref "LED25") (pin "K1") (pinfunction "C_K1") (pintype "passive"))
      (node (ref "LED33") (pin "K") (pinfunction "C_K") (pintype "passive"))
      (node (ref "LED33") (pin "K1") (pinfunction "C_K1") (pintype "passive"))
      (node (ref "LED41") (pin "K") (pinfunction "C_K") (pintype "passive"))
      (node (ref "LED41") (pin "K1") (pinfunction "C_K1") (pintype "passive"))
      (node (ref "LED49") (pin "K") (pinfunction "C_K") (pintype "passive"))
      (node (ref "LED49") (pin "K1") (pinfunction "C_K1") (pintype "passive"))
      (node (ref "LED57") (pin "K") (pinfunction "C_K") (pintype "passive"))
      (node (ref "LED57") (pin "K1") (pinfunction "C_K1") (pintype "passive"))
      (node (ref "LED9") (pin "K") (pinfunction "C_K") (pintype "passive"))
      (node (ref "LED9") (pin "K1") (pinfunction "C_K1") (pintype "passive"))
      (node (ref "Q11") (pin "3") (pinfunction "D_3") (pintype "passive"))
      (node (ref "R1") (pin "2") (pinfunction "P$2_2") (pintype "passive"))
      (node (ref "R2") (pin "1") (pinfunction "P$1_1") (pintype "passive"))
    )
    (net (code "11") (name "/COMMS_DOWN") (class "Default")
      (node (ref "IC1") (pin "19") (pinfunction "PB1_19") (pintype "bidirectional"))
      (node (ref "JP4") (pin "3") (pinfunction "3_3") (pintype "passive"))
    )
    (net (code "12") (name "/COMMS_LEFT") (class "Default")
      (node (ref "IC1") (pin "3") (pinfunction "PC14_3") (pintype "bidirectional"))
      (node (ref "JP2") (pin "3") (pinfunction "3_3") (pintype "passive"))
    )
    (net (code "13") (name "/COMMS_RIGHT") (class "Default")
      (node (ref "IC1") (pin "2") (pinfunction "PC13_2") (pintype "bidirectional"))
      (node (ref "JP3") (pin "3") (pinfunction "3_3") (pintype "passive"))
    )
    (net (code "14") (name "/COMMS_UP") (class "Default")
      (node (ref "IC1") (pin "18") (pinfunction "PB0_18") (pintype "bidirectional"))
      (node (ref "JP1") (pin "3") (pinfunction "3_3") (pintype "passive"))
    )
    (net (code "15") (name "/G_UART") (class "Default")
      (node (ref "IC1") (pin "31") (pinfunction "PA10_31") (pintype "bidirectional"))
      (node (ref "JP1") (pin "6") (pinfunction "6_6") (pintype "passive"))
      (node (ref "JP2") (pin "6") (pinfunction "6_6") (pintype "passive"))
      (node (ref "JP3") (pin "6") (pinfunction "6_6") (pintype "passive"))
      (node (ref "JP4") (pin "6") (pinfunction "6_6") (pintype "passive"))
      (node (ref "JP5") (pin "3") (pinfunction "3_3") (pintype "passive"))
    )
    (net (code "16") (name "/NRST") (class "Default")
      (node (ref "IC1") (pin "7") (pinfunction "NRST_7") (pintype "input"))
      (node (ref "J1") (pin "10") (pinfunction "NRST_10") (pintype "bidirectional"))
      (node (ref "JP7") (pin "3") (pinfunction "RST_3") (pintype "output"))
    )
    (net (code "17") (name "/RFET1") (class "Default")
      (node (ref "IC1") (pin "33") (pinfunction "PA12_33") (pintype "bidirectional"))
      (node (ref "Q1") (pin "1") (pinfunction "G_1") (pintype "passive"))
      (node (ref "RN3") (pin "5") (pinfunction "2_5") (pintype "passive"))
    )
    (net (code "18") (name "/RFET2") (class "Default")
      (node (ref "Q2") (pin "1") (pinfunction "G_1") (pintype "passive"))
      (node (ref "RN3") (pin "6") (pinfunction "2_6") (pintype "passive"))
      (node (ref "SJ2") (pin "2") (pinfunction "2_2") (pintype "passive"))
    )
    (net (code "19") (name "/RFET3") (class "Default")
      (node (ref "Q3") (pin "1") (pinfunction "G_1") (pintype "passive"))
      (node (ref "RN3") (pin "7") (pinfunction "2_7") (pintype "passive"))
      (node (ref "SJ1") (pin "2") (pinfunction "2_2") (pintype "passive"))
    )
    (net (code "20") (name "/RFET4") (class "Default")
      (node (ref "IC1") (pin "38") (pinfunction "PA15_38") (pintype "bidirectional"))
      (node (ref "Q12") (pin "1") (pinfunction "G_1") (pintype "passive"))
      (node (ref "RN3") (pin "8") (pinfunction "2_8") (pintype "passive"))
    )
    (net (code "21") (name "/RFET5") (class "Default")
      (node (ref "IC1") (pin "29") (pinfunction "PA8_29") (pintype "bidirectional"))
      (node (ref "Q13") (pin "1") (pinfunction "G_1") (pintype "passive"))
      (node (ref "RN4") (pin "5") (pinfunction "2_5") (pintype "passive"))
    )
    (net (code "22") (name "/RFET6") (class "Default")
      (node (ref "IC1") (pin "30") (pinfunction "PA9_30") (pintype "bidirectional"))
      (node (ref "JP5") (pin "2") (pinfunction "2_2") (pintype "passive"))
      (node (ref "Q14") (pin "1") (pinfunction "G_1") (pintype "passive"))
      (node (ref "RN4") (pin "8") (pinfunction "2_8") (pintype "passive"))
    )
    (net (code "23") (name "/RFET7") (class "Default")
      (node (ref "IC1") (pin "28") (pinfunction "PB15_28") (pintype "bidirectional"))
      (node (ref "Q15") (pin "1") (pinfunction "G_1") (pintype "passive"))
      (node (ref "RN4") (pin "7") (pinfunction "2_7") (pintype "passive"))
    )
    (net (code "24") (name "/RFET8") (class "Default")
      (node (ref "IC1") (pin "32") (pinfunction "PA11_32") (pintype "bidirectional"))
      (node (ref "Q16") (pin "1") (pinfunction "G_1") (pintype "passive"))
      (node (ref "RN4") (pin "6") (pinfunction "2_6") (pintype "passive"))
    )
    (net (code "25") (name "/SHIFT_LEFT") (class "Default")
      (node (ref "IC1") (pin "36") (pinfunction "PF7_36") (pintype "bidirectional"))
      (node (ref "JP2") (pin "4") (pinfunction "4_4") (pintype "passive"))
    )
    (net (code "26") (name "/SHIFT_RIGHT") (class "Default")
      (node (ref "IC1") (pin "35") (pinfunction "PF6_35") (pintype "bidirectional"))
      (node (ref "JP3") (pin "4") (pinfunction "4_4") (pintype "passive"))
    )
    (net (code "27") (name "/SWCLK") (class "Default")
      (node (ref "IC1") (pin "37") (pinfunction "PA14_37") (pintype "bidirectional"))
      (node (ref "J1") (pin "4") (pinfunction "SWCLK_4") (pintype "bidirectional"))
      (node (ref "JP7") (pin "4") (pinfunction "SWCLK_4") (pintype "output"))
      (node (ref "SJ1") (pin "1") (pinfunction "1_1") (pintype "passive"))
    )
    (net (code "28") (name "/SWDAT") (class "Default")
      (node (ref "IC1") (pin "34") (pinfunction "PA13_34") (pintype "bidirectional"))
      (node (ref "J1") (pin "2") (pinfunction "SWDAT_2") (pintype "bidirectional"))
      (node (ref "JP7") (pin "2") (pinfunction "SWDAT_2") (pintype "bidirectional"))
      (node (ref "SJ2") (pin "1") (pinfunction "1_1") (pintype "passive"))
    )
    (net (code "29") (name "CFET1") (class "Default")
      (node (ref "IC1") (pin "10") (pinfunction "PA0_10") (pintype "bidirectional"))
      (node (ref "Q11") (pin "1") (pinfunction "G_1") (pintype "passive"))
    )
    (net (code "30") (name "CFET2") (class "Default")
      (node (ref "IC1") (pin "11") (pinfunction "PA1_11") (pintype "bidirectional"))
      (node (ref "Q10") (pin "1") (pinfunction "G_1") (pintype "passive"))
    )
    (net (code "31") (name "CFET3") (class "Default")
      (node (ref "IC1") (pin "12") (pinfunction "PA2_12") (pintype "bidirectional"))
      (node (ref "Q9") (pin "1") (pinfunction "G_1") (pintype "passive"))
    )
    (net (code "32") (name "CFET4") (class "Default")
      (node (ref "IC1") (pin "13") (pinfunction "PA3_13") (pintype "bidirectional"))
      (node (ref "Q8") (pin "1") (pinfunction "G_1") (pintype "passive"))
    )
    (net (code "33") (name "CFET5") (class "Default")
      (node (ref "IC1") (pin "14") (pinfunction "PA4_14") (pintype "bidirectional"))
      (node (ref "Q7") (pin "1") (pinfunction "G_1") (pintype "passive"))
    )
    (net (code "34") (name "CFET6") (class "Default")
      (node (ref "IC1") (pin "15") (pinfunction "PA5_15") (pintype "bidirectional"))
      (node (ref "Q6") (pin "1") (pinfunction "G_1") (pintype "passive"))
    )
    (net (code "35") (name "CFET7") (class "Default")
      (node (ref "IC1") (pin "16") (pinfunction "PA6_16") (pintype "bidirectional"))
      (node (ref "Q5") (pin "1") (pinfunction "G_1") (pintype "passive"))
    )
    (net (code "36") (name "CFET8") (class "Default")
      (node (ref "IC1") (pin "17") (pinfunction "PA7_17") (pintype "bidirectional"))
      (node (ref "Q4") (pin "1") (pinfunction "G_1") (pintype "passive"))
    )
    (net (code "37") (name "GND") (class "Default")
      (node (ref "C1") (pin "-") (pinfunction "-_-") (pintype "passive"))
      (node (ref "C10") (pin "2") (pinfunction "2_2") (pintype "passive"))
      (node (ref "C11") (pin "2") (pinfunction "2_2") (pintype "passive"))
      (node (ref "C12") (pin "2") (pinfunction "2_2") (pintype "passive"))
      (node (ref "C13") (pin "2") (pinfunction "2_2") (pintype "passive"))
      (node (ref "C14") (pin "2") (pinfunction "2_2") (pintype "passive"))
      (node (ref "C15") (pin "2") (pinfunction "2_2") (pintype "passive"))
      (node (ref "C16") (pin "-") (pinfunction "-_-") (pintype "passive"))
      (node (ref "C2") (pin "2") (pinfunction "2_2") (pintype "passive"))
      (node (ref "C3") (pin "2") (pinfunction "2_2") (pintype "passive"))
      (node (ref "C4") (pin "2") (pinfunction "2_2") (pintype "passive"))
      (node (ref "C5") (pin "2") (pinfunction "2_2") (pintype "passive"))
      (node (ref "C6") (pin "2") (pinfunction "2_2") (pintype "passive"))
      (node (ref "C7") (pin "2") (pinfunction "2_2") (pintype "passive"))
      (node (ref "C8") (pin "2") (pinfunction "2_2") (pintype "passive"))
      (node (ref "C9") (pin "2") (pinfunction "2_2") (pintype "passive"))
      (node (ref "IC1") (pin "23") (pinfunction "VSS_23") (pintype "power_in"))
      (node (ref "IC1") (pin "47") (pinfunction "VSS1_47") (pintype "power_in"))
      (node (ref "IC1") (pin "8") (pinfunction "VSSA_8") (pintype "power_in"))
      (node (ref "J1") (pin "3") (pinfunction "GND1_3") (pintype "power_in"))
      (node (ref "J1") (pin "5") (pinfunction "GND2_5") (pintype "power_in"))
      (node (ref "J1") (pin "9") (pinfunction "GNDD_9") (pintype "power_in"))
      (node (ref "JP1") (pin "2") (pinfunction "2_2") (pintype "passive"))
      (node (ref "JP1") (pin "7") (pinfunction "7_7") (pintype "passive"))
      (node (ref "JP2") (pin "2") (pinfunction "2_2") (pintype "passive"))
      (node (ref "JP2") (pin "7") (pinfunction "7_7") (pintype "passive"))
      (node (ref "JP3") (pin "2") (pinfunction "2_2") (pintype "passive"))
      (node (ref "JP3") (pin "7") (pinfunction "7_7") (pintype "passive"))
      (node (ref "JP4") (pin "2") (pinfunction "2_2") (pintype "passive"))
      (node (ref "JP4") (pin "7") (pinfunction "7_7") (pintype "passive"))
      (node (ref "JP5") (pin "6") (pinfunction "6_6") (pintype "passive"))
      (node (ref "JP6") (pin "1") (pinfunction "1_1") (pintype "passive"))
      (node (ref "JP7") (pin "5") (pinfunction "GND_5") (pintype "power_in"))
      (node (ref "Q10") (pin "2") (pinfunction "S_2") (pintype "passive"))
      (node (ref "Q11") (pin "2") (pinfunction "S_2") (pintype "passive"))
      (node (ref "Q17") (pin "GND") (pinfunction "GND_GND") (pintype "input"))
      (node (ref "Q4") (pin "2") (pinfunction "S_2") (pintype "passive"))
      (node (ref "Q5") (pin "2") (pinfunction "S_2") (pintype "passive"))
      (node (ref "Q6") (pin "2") (pinfunction "S_2") (pintype "passive"))
      (node (ref "Q7") (pin "2") (pinfunction "S_2") (pintype "passive"))
      (node (ref "Q8") (pin "2") (pinfunction "S_2") (pintype "passive"))
      (node (ref "Q9") (pin "2") (pinfunction "S_2") (pintype "passive"))
      (node (ref "R1") (pin "1") (pinfunction "P$1_1") (pintype "passive"))
      (node (ref "R3") (pin "1") (pinfunction "P$1_1") (pintype "passive"))
      (node (ref "R4") (pin "1") (pinfunction "P$1_1") (pintype "passive"))
      (node (ref "R5") (pin "1") (pinfunction "P$1_1") (pintype "passive"))
      (node (ref "R6") (pin "1") (pinfunction "P$1_1") (pintype "passive"))
      (node (ref "R7") (pin "1") (pinfunction "P$1_1") (pintype "passive"))
      (node (ref "R8") (pin "1") (pinfunction "P$1_1") (pintype "passive"))
      (node (ref "R9") (pin "1") (pinfunction "P$1_1") (pintype "passive"))
    )
    (net (code "38") (name "Net-(IC1-BOOT0)") (class "Default")
      (node (ref "IC1") (pin "44") (pinfunction "BOOT0_44") (pintype "input"))
      (node (ref "JP6") (pin "2") (pinfunction "2_2") (pintype "passive"))
      (node (ref "R10") (pin "1") (pinfunction "P$1_1") (pintype "passive"))
    )
    (net (code "39") (name "Net-(IC1-PC15)") (class "Default")
      (node (ref "IC1") (pin "4") (pinfunction "PC15_4") (pintype "bidirectional"))
      (node (ref "R2") (pin "2") (pinfunction "P$2_2") (pintype "passive"))
    )
    (net (code "40") (name "Net-(Q1-D)") (class "Default")
      (node (ref "Q1") (pin "3") (pinfunction "D_3") (pintype "passive"))
      (node (ref "R11") (pin "2") (pinfunction "P$2_2") (pintype "passive"))
    )
    (net (code "41") (name "Net-(Q2-D)") (class "Default")
      (node (ref "Q2") (pin "3") (pinfunction "D_3") (pintype "passive"))
      (node (ref "R12") (pin "2") (pinfunction "P$2_2") (pintype "passive"))
    )
    (net (code "42") (name "Net-(Q3-D)") (class "Default")
      (node (ref "Q3") (pin "3") (pinfunction "D_3") (pintype "passive"))
      (node (ref "R13") (pin "2") (pinfunction "P$2_2") (pintype "passive"))
    )
    (net (code "43") (name "Net-(Q12-D)") (class "Default")
      (node (ref "Q12") (pin "3") (pinfunction "D_3") (pintype "passive"))
      (node (ref "R14") (pin "2") (pinfunction "P$2_2") (pintype "passive"))
    )
    (net (code "44") (name "Net-(Q13-D)") (class "Default")
      (node (ref "Q13") (pin "3") (pinfunction "D_3") (pintype "passive"))
      (node (ref "R15") (pin "2") (pinfunction "P$2_2") (pintype "passive"))
    )
    (net (code "45") (name "Net-(Q14-D)") (class "Default")
      (node (ref "Q14") (pin "3") (pinfunction "D_3") (pintype "passive"))
      (node (ref "R16") (pin "2") (pinfunction "P$2_2") (pintype "passive"))
    )
    (net (code "46") (name "Net-(Q15-D)") (class "Default")
      (node (ref "Q15") (pin "3") (pinfunction "D_3") (pintype "passive"))
      (node (ref "R17") (pin "2") (pinfunction "P$2_2") (pintype "passive"))
    )
    (net (code "47") (name "Net-(Q16-D)") (class "Default")
      (node (ref "Q16") (pin "3") (pinfunction "D_3") (pintype "passive"))
      (node (ref "R18") (pin "2") (pinfunction "P$2_2") (pintype "passive"))
    )
    (net (code "48") (name "ROW1") (class "Default")
      (node (ref "IC1") (pin "5") (pinfunction "PF0_5") (pintype "bidirectional"))
      (node (ref "LED57") (pin "A") (pinfunction "A_A") (pintype "passive"))
      (node (ref "LED57") (pin "A1") (pinfunction "A_A1") (pintype "passive"))
      (node (ref "LED58") (pin "A") (pinfunction "A_A") (pintype "passive"))
      (node (ref "LED58") (pin "A1") (pinfunction "A_A1") (pintype "passive"))
      (node (ref "LED59") (pin "A") (pinfunction "A_A") (pintype "passive"))
      (node (ref "LED59") (pin "A1") (pinfunction "A_A1") (pintype "passive"))
      (node (ref "LED60") (pin "A") (pinfunction "A_A") (pintype "passive"))
      (node (ref "LED60") (pin "A1") (pinfunction "A_A1") (pintype "passive"))
      (node (ref "LED61") (pin "A") (pinfunction "A_A") (pintype "passive"))
      (node (ref "LED61") (pin "A1") (pinfunction "A_A1") (pintype "passive"))
      (node (ref "LED62") (pin "A") (pinfunction "A_A") (pintype "passive"))
      (node (ref "LED62") (pin "A1") (pinfunction "A_A1") (pintype "passive"))
      (node (ref "LED63") (pin "A") (pinfunction "A_A") (pintype "passive"))
      (node (ref "LED63") (pin "A1") (pinfunction "A_A1") (pintype "passive"))
      (node (ref "LED64") (pin "A") (pinfunction "A_A") (pintype "passive"))
      (node (ref "LED64") (pin "A1") (pinfunction "A_A1") (pintype "passive"))
      (node (ref "R11") (pin "1") (pinfunction "P$1_1") (pintype "passive"))
    )
    (net (code "49") (name "ROW2") (class "Default")
      (node (ref "IC1") (pin "6") (pinfunction "PF1_6") (pintype "bidirectional"))
      (node (ref "LED49") (pin "A") (pinfunction "A_A") (pintype "passive"))
      (node (ref "LED49") (pin "A1") (pinfunction "A_A1") (pintype "passive"))
      (node (ref "LED50") (pin "A") (pinfunction "A_A") (pintype "passive"))
      (node (ref "LED50") (pin "A1") (pinfunction "A_A1") (pintype "passive"))
      (node (ref "LED51") (pin "A") (pinfunction "A_A") (pintype "passive"))
      (node (ref "LED51") (pin "A1") (pinfunction "A_A1") (pintype "passive"))
      (node (ref "LED52") (pin "A") (pinfunction "A_A") (pintype "passive"))
      (node (ref "LED52") (pin "A1") (pinfunction "A_A1") (pintype "passive"))
      (node (ref "LED53") (pin "A") (pinfunction "A_A") (pintype "passive"))
      (node (ref "LED53") (pin "A1") (pinfunction "A_A1") (pintype "passive"))
      (node (ref "LED54") (pin "A") (pinfunction "A_A") (pintype "passive"))
      (node (ref "LED54") (pin "A1") (pinfunction "A_A1") (pintype "passive"))
      (node (ref "LED55") (pin "A") (pinfunction "A_A") (pintype "passive"))
      (node (ref "LED55") (pin "A1") (pinfunction "A_A1") (pintype "passive"))
      (node (ref "LED56") (pin "A") (pinfunction "A_A") (pintype "passive"))
      (node (ref "LED56") (pin "A1") (pinfunction "A_A1") (pintype "passive"))
      (node (ref "R12") (pin "1") (pinfunction "P$1_1") (pintype "passive"))
    )
    (net (code "50") (name "ROW3") (class "Default")
      (node (ref "IC1") (pin "20") (pinfunction "PB2_20") (pintype "bidirectional"))
      (node (ref "LED41") (pin "A") (pinfunction "A_A") (pintype "passive"))
      (node (ref "LED41") (pin "A1") (pinfunction "A_A1") (pintype "passive"))
      (node (ref "LED42") (pin "A") (pinfunction "A_A") (pintype "passive"))
      (node (ref "LED42") (pin "A1") (pinfunction "A_A1") (pintype "passive"))
      (node (ref "LED43") (pin "A") (pinfunction "A_A") (pintype "passive"))
      (node (ref "LED43") (pin "A1") (pinfunction "A_A1") (pintype "passive"))
      (node (ref "LED44") (pin "A") (pinfunction "A_A") (pintype "passive"))
      (node (ref "LED44") (pin "A1") (pinfunction "A_A1") (pintype "passive"))
      (node (ref "LED45") (pin "A") (pinfunction "A_A") (pintype "passive"))
      (node (ref "LED45") (pin "A1") (pinfunction "A_A1") (pintype "passive"))
      (node (ref "LED46") (pin "A") (pinfunction "A_A") (pintype "passive"))
      (node (ref "LED46") (pin "A1") (pinfunction "A_A1") (pintype "passive"))
      (node (ref "LED47") (pin "A") (pinfunction "A_A") (pintype "passive"))
      (node (ref "LED47") (pin "A1") (pinfunction "A_A1") (pintype "passive"))
      (node (ref "LED48") (pin "A") (pinfunction "A_A") (pintype "passive"))
      (node (ref "LED48") (pin "A1") (pinfunction "A_A1") (pintype "passive"))
      (node (ref "R13") (pin "1") (pinfunction "P$1_1") (pintype "passive"))
    )
    (net (code "51") (name "ROW4") (class "Default")
      (node (ref "IC1") (pin "39") (pinfunction "PB3_39") (pintype "bidirectional"))
      (node (ref "LED33") (pin "A") (pinfunction "A_A") (pintype "passive"))
      (node (ref "LED33") (pin "A1") (pinfunction "A_A1") (pintype "passive"))
      (node (ref "LED34") (pin "A") (pinfunction "A_A") (pintype "passive"))
      (node (ref "LED34") (pin "A1") (pinfunction "A_A1") (pintype "passive"))
      (node (ref "LED35") (pin "A") (pinfunction "A_A") (pintype "passive"))
      (node (ref "LED35") (pin "A1") (pinfunction "A_A1") (pintype "passive"))
      (node (ref "LED36") (pin "A") (pinfunction "A_A") (pintype "passive"))
      (node (ref "LED36") (pin "A1") (pinfunction "A_A1") (pintype "passive"))
      (node (ref "LED37") (pin "A") (pinfunction "A_A") (pintype "passive"))
      (node (ref "LED37") (pin "A1") (pinfunction "A_A1") (pintype "passive"))
      (node (ref "LED38") (pin "A") (pinfunction "A_A") (pintype "passive"))
      (node (ref "LED38") (pin "A1") (pinfunction "A_A1") (pintype "passive"))
      (node (ref "LED39") (pin "A") (pinfunction "A_A") (pintype "passive"))
      (node (ref "LED39") (pin "A1") (pinfunction "A_A1") (pintype "passive"))
      (node (ref "LED40") (pin "A") (pinfunction "A_A") (pintype "passive"))
      (node (ref "LED40") (pin "A1") (pinfunction "A_A1") (pintype "passive"))
      (node (ref "R14") (pin "1") (pinfunction "P$1_1") (pintype "passive"))
    )
    (net (code "52") (name "ROW5") (class "Default")
      (node (ref "IC1") (pin "40") (pinfunction "PB4_40") (pintype "bidirectional"))
      (node (ref "LED25") (pin "A") (pinfunction "A_A") (pintype "passive"))
      (node (ref "LED25") (pin "A1") (pinfunction "A_A1") (pintype "passive"))
      (node (ref "LED26") (pin "A") (pinfunction "A_A") (pintype "passive"))
      (node (ref "LED26") (pin "A1") (pinfunction "A_A1") (pintype "passive"))
      (node (ref "LED27") (pin "A") (pinfunction "A_A") (pintype "passive"))
      (node (ref "LED27") (pin "A1") (pinfunction "A_A1") (pintype "passive"))
      (node (ref "LED28") (pin "A") (pinfunction "A_A") (pintype "passive"))
      (node (ref "LED28") (pin "A1") (pinfunction "A_A1") (pintype "passive"))
      (node (ref "LED29") (pin "A") (pinfunction "A_A") (pintype "passive"))
      (node (ref "LED29") (pin "A1") (pinfunction "A_A1") (pintype "passive"))
      (node (ref "LED30") (pin "A") (pinfunction "A_A") (pintype "passive"))
      (node (ref "LED30") (pin "A1") (pinfunction "A_A1") (pintype "passive"))
      (node (ref "LED31") (pin "A") (pinfunction "A_A") (pintype "passive"))
      (node (ref "LED31") (pin "A1") (pinfunction "A_A1") (pintype "passive"))
      (node (ref "LED32") (pin "A") (pinfunction "A_A") (pintype "passive"))
      (node (ref "LED32") (pin "A1") (pinfunction "A_A1") (pintype "passive"))
      (node (ref "R15") (pin "1") (pinfunction "P$1_1") (pintype "passive"))
    )
    (net (code "53") (name "ROW6") (class "Default")
      (node (ref "IC1") (pin "41") (pinfunction "PB5_41") (pintype "bidirectional"))
      (node (ref "LED17") (pin "A") (pinfunction "A_A") (pintype "passive"))
      (node (ref "LED17") (pin "A1") (pinfunction "A_A1") (pintype "passive"))
      (node (ref "LED18") (pin "A") (pinfunction "A_A") (pintype "passive"))
      (node (ref "LED18") (pin "A1") (pinfunction "A_A1") (pintype "passive"))
      (node (ref "LED19") (pin "A") (pinfunction "A_A") (pintype "passive"))
      (node (ref "LED19") (pin "A1") (pinfunction "A_A1") (pintype "passive"))
      (node (ref "LED20") (pin "A") (pinfunction "A_A") (pintype "passive"))
      (node (ref "LED20") (pin "A1") (pinfunction "A_A1") (pintype "passive"))
      (node (ref "LED21") (pin "A") (pinfunction "A_A") (pintype "passive"))
      (node (ref "LED21") (pin "A1") (pinfunction "A_A1") (pintype "passive"))
      (node (ref "LED22") (pin "A") (pinfunction "A_A") (pintype "passive"))
      (node (ref "LED22") (pin "A1") (pinfunction "A_A1") (pintype "passive"))
      (node (ref "LED23") (pin "A") (pinfunction "A_A") (pintype "passive"))
      (node (ref "LED23") (pin "A1") (pinfunction "A_A1") (pintype "passive"))
      (node (ref "LED24") (pin "A") (pinfunction "A_A") (pintype "passive"))
      (node (ref "LED24") (pin "A1") (pinfunction "A_A1") (pintype "passive"))
      (node (ref "R16") (pin "1") (pinfunction "P$1_1") (pintype "passive"))
    )
    (net (code "54") (name "ROW7") (class "Default")
      (node (ref "IC1") (pin "42") (pinfunction "PB6_42") (pintype "bidirectional"))
      (node (ref "LED10") (pin "A") (pinfunction "A_A") (pintype "passive"))
      (node (ref "LED10") (pin "A1") (pinfunction "A_A1") (pintype "passive"))
      (node (ref "LED11") (pin "A") (pinfunction "A_A") (pintype "passive"))
      (node (ref "LED11") (pin "A1") (pinfunction "A_A1") (pintype "passive"))
      (node (ref "LED12") (pin "A") (pinfunction "A_A") (pintype "passive"))
      (node (ref "LED12") (pin "A1") (pinfunction "A_A1") (pintype "passive"))
      (node (ref "LED13") (pin "A") (pinfunction "A_A") (pintype "passive"))
      (node (ref "LED13") (pin "A1") (pinfunction "A_A1") (pintype "passive"))
      (node (ref "LED14") (pin "A") (pinfunction "A_A") (pintype "passive"))
      (node (ref "LED14") (pin "A1") (pinfunction "A_A1") (pintype "passive"))
      (node (ref "LED15") (pin "A") (pinfunction "A_A") (pintype "passive"))
      (node (ref "LED15") (pin "A1") (pinfunction "A_A1") (pintype "passive"))
      (node (ref "LED16") (pin "A") (pinfunction "A_A") (pintype "passive"))
      (node (ref "LED16") (pin "A1") (pinfunction "A_A1") (pintype "passive"))
      (node (ref "LED9") (pin "A") (pinfunction "A_A") (pintype "passive"))
      (node (ref "LED9") (pin "A1") (pinfunction "A_A1") (pintype "passive"))
      (node (ref "R17") (pin "1") (pinfunction "P$1_1") (pintype "passive"))
    )
    (net (code "55") (name "ROW8") (class "Default")
      (node (ref "IC1") (pin "43") (pinfunction "PB7_43") (pintype "bidirectional"))
      (node (ref "LED1") (pin "A") (pinfunction "A_A") (pintype "passive"))
      (node (ref "LED1") (pin "A1") (pinfunction "A_A1") (pintype "passive"))
      (node (ref "LED2") (pin "A") (pinfunction "A_A") (pintype "passive"))
      (node (ref "LED2") (pin "A1") (pinfunction "A_A1") (pintype "passive"))
      (node (ref "LED3") (pin "A") (pinfunction "A_A") (pintype "passive"))
      (node (ref "LED3") (pin "A1") (pinfunction "A_A1") (pintype "passive"))
      (node (ref "LED4") (pin "A") (pinfunction "A_A") (pintype "passive"))
      (node (ref "LED4") (pin "A1") (pinfunction "A_A1") (pintype "passive"))
      (node (ref "LED5") (pin "A") (pinfunction "A_A") (pintype "passive"))
      (node (ref "LED5") (pin "A1") (pinfunction "A_A1") (pintype "passive"))
      (node (ref "LED6") (pin "A") (pinfunction "A_A") (pintype "passive"))
      (node (ref "LED6") (pin "A1") (pinfunction "A_A1") (pintype "passive"))
      (node (ref "LED7") (pin "A") (pinfunction "A_A") (pintype "passive"))
      (node (ref "LED7") (pin "A1") (pinfunction "A_A1") (pintype "passive"))
      (node (ref "LED8") (pin "A") (pinfunction "A_A") (pintype "passive"))
      (node (ref "LED8") (pin "A1") (pinfunction "A_A1") (pintype "passive"))
      (node (ref "R18") (pin "1") (pinfunction "P$1_1") (pintype "passive"))
    )
    (net (code "56") (name "unconnected-(J1-KEY-Pad7)") (class "Default")
      (node (ref "J1") (pin "7") (pinfunction "KEY_7") (pintype "bidirectional"))
    )
    (net (code "57") (name "unconnected-(J1-NC-Pad8)") (class "Default")
      (node (ref "J1") (pin "8") (pinfunction "NC_8") (pintype "no_connect"))
    )
    (net (code "58") (name "unconnected-(J1-SWO-Pad6)") (class "Default")
      (node (ref "J1") (pin "6") (pinfunction "SWO_6") (pintype "bidirectional"))
    )
    (net (code "59") (name "unconnected-(JP1-Pad4)") (class "Default")
      (node (ref "JP1") (pin "4") (pinfunction "4_4") (pintype "passive"))
    )
    (net (code "60") (name "unconnected-(JP4-Pad4)") (class "Default")
      (node (ref "JP4") (pin "4") (pinfunction "4_4") (pintype "passive"))
    )
    (net (code "61") (name "unconnected-(JP5-Pad1)") (class "Default")
      (node (ref "JP5") (pin "1") (pinfunction "1_1") (pintype "passive"))
    )
    (net (code "62") (name "unconnected-(JP5-Pad5)") (class "Default")
      (node (ref "JP5") (pin "5") (pinfunction "5_5") (pintype "passive"))
    )
    (net (code "63") (name "unconnected-(JP7-SWO-Pad6)") (class "Default")
      (node (ref "JP7") (pin "6") (pinfunction "SWO_6") (pintype "input"))
    )
  )
)
